# Power_Board_R1.net
KiCad netlist of a schematic drawn in Altium Designer
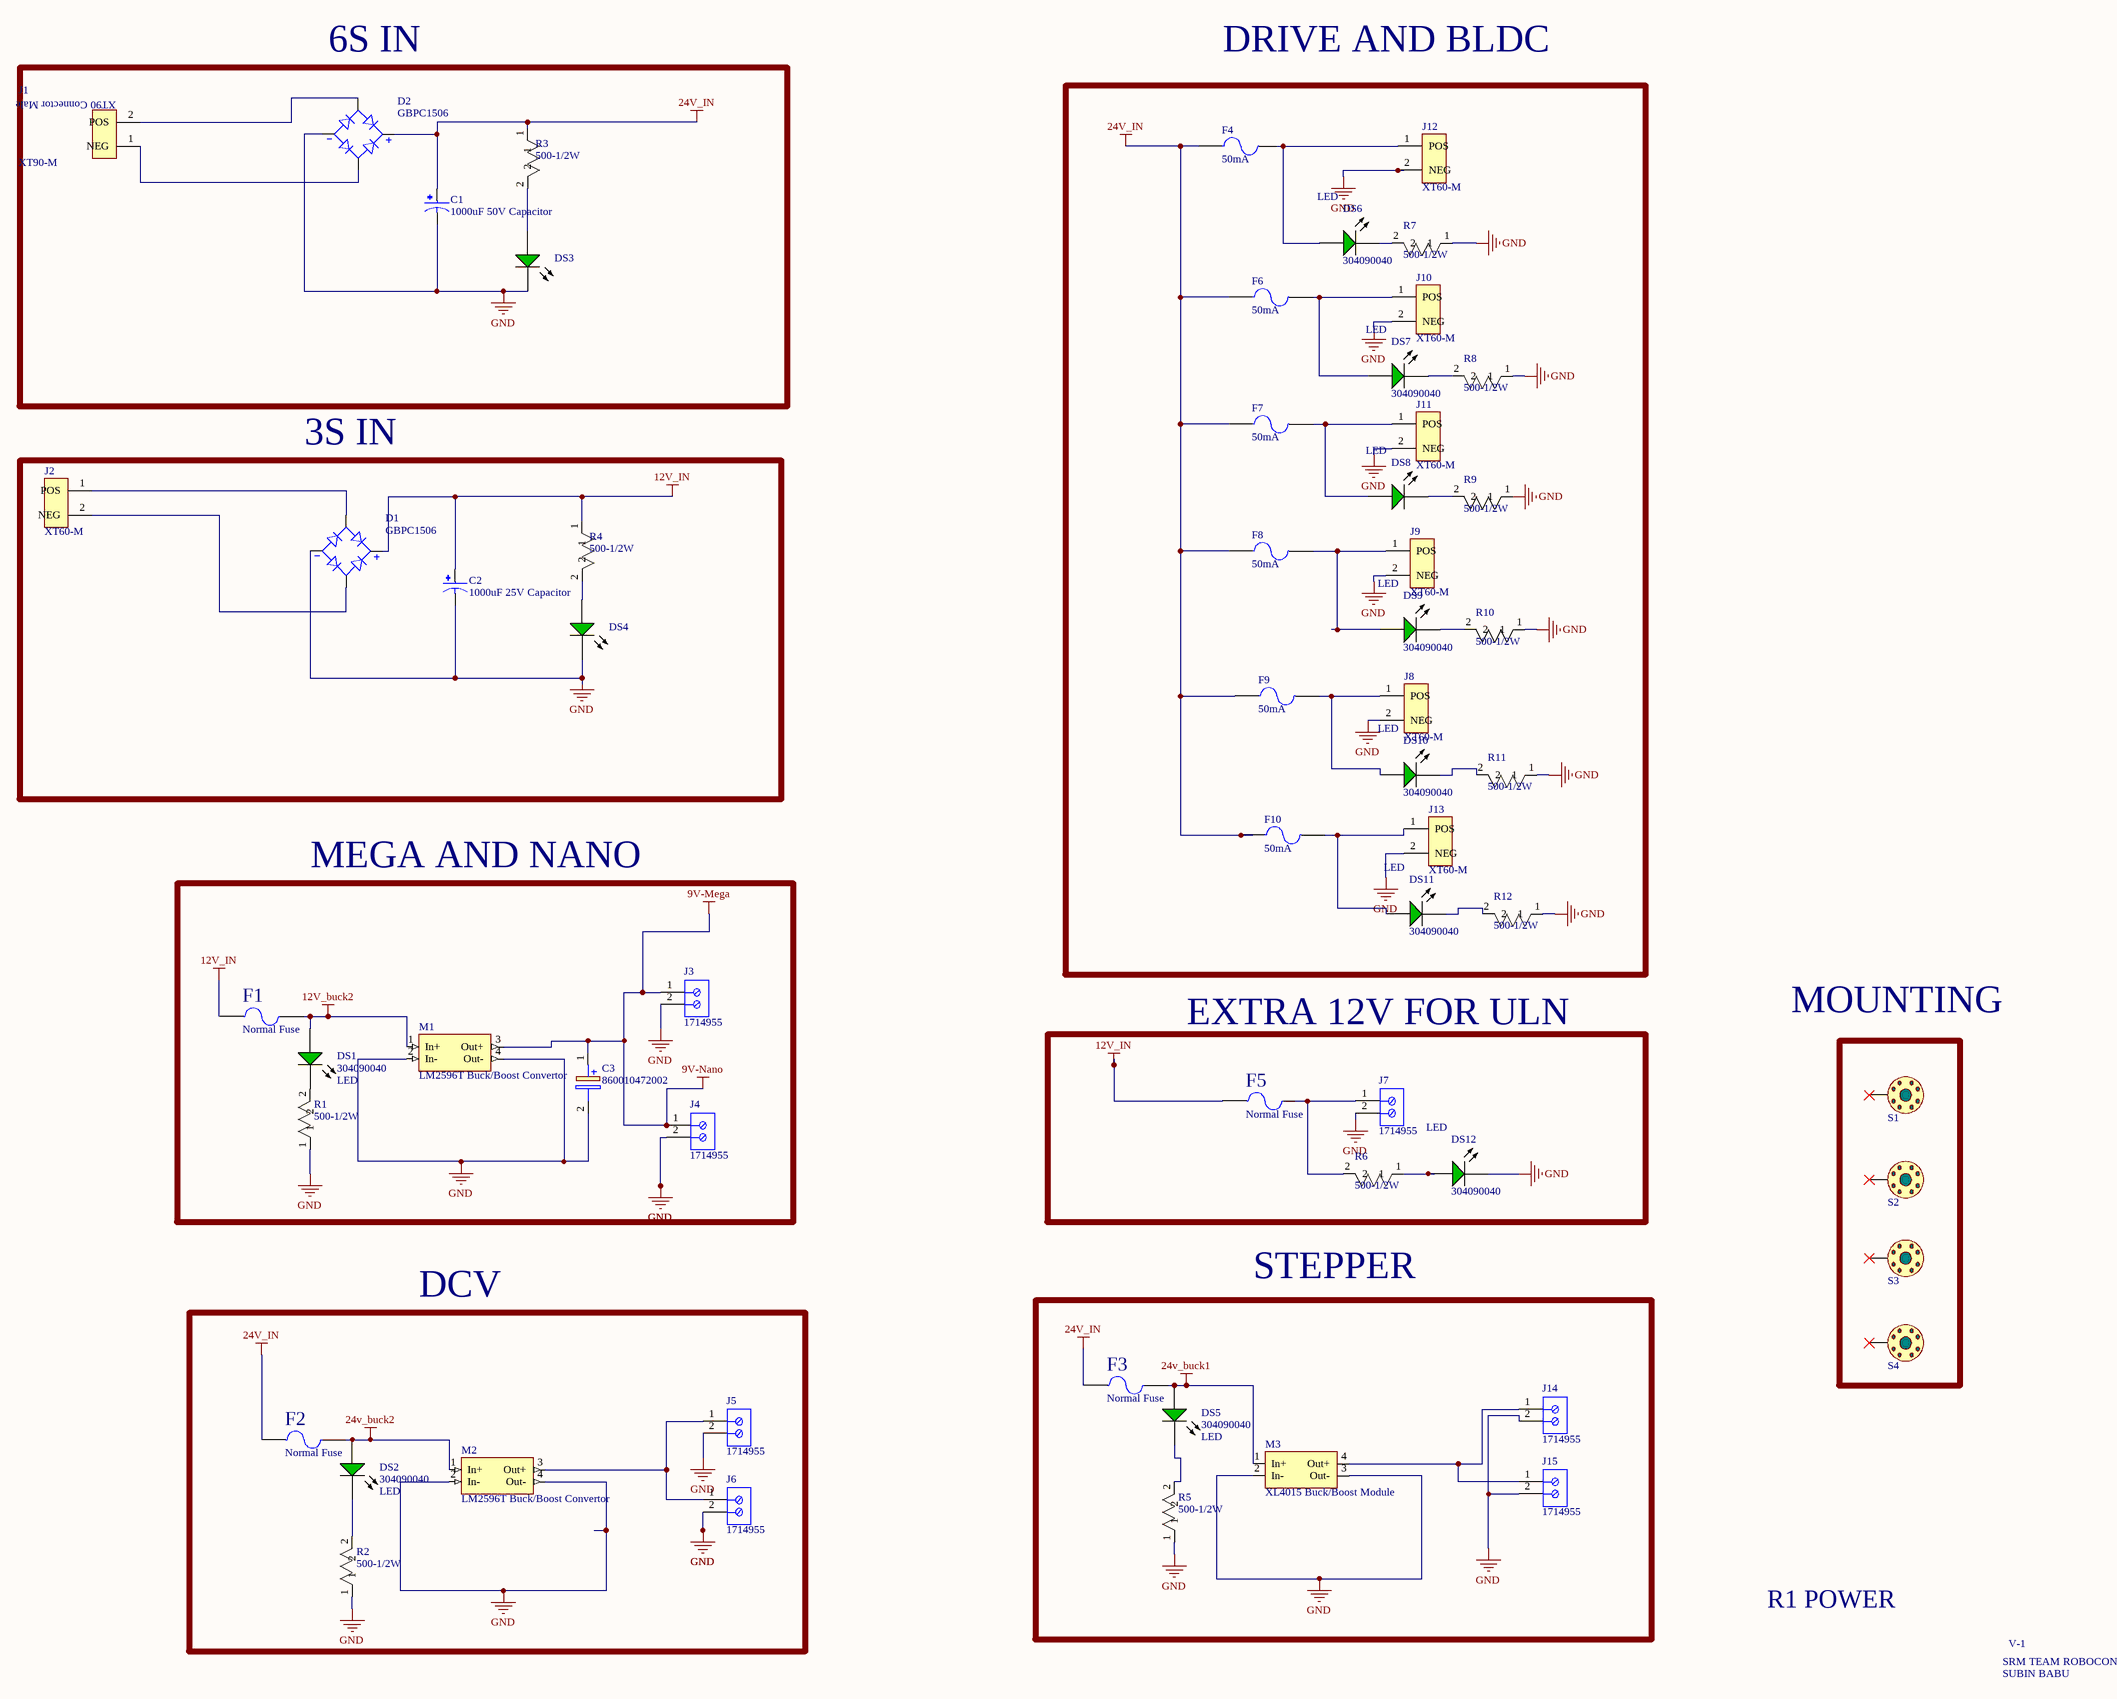
[diagram p0: Power_Board_R1.SchDoc]

(export (version "E")
  (design (tool "Eeschema 10.0.6"))
  (components
    (comp (ref "C1")
      (value "1000uF 50V Capacitor")
      (footprint "1000uF 50V Capacitor")
      (description "CAP ALUM 1000UF 20% 50V RADIAL")
      (fields (field (name "MF") "Panasonic") (field (name "MP") "EEU-HD1H102B"))
      (libsource (lib "R1") (part "1000uF 50V Capacitor"))
    )
    (comp (ref "C2")
      (value "1000uF 25V Capacitor")
      (footprint "1000uF 25V Capacitor")
      (description "CAP ALUM 1000UF 20% 25V RADIAL")
      (fields (field (name "MP") "EEUTA1E102LB") (field (name "MF") "Panasonic"))
      (libsource (lib "R1") (part "1000uF 25V Capacitor"))
    )
    (comp (ref "C3")
      (value "860010472002")
      (footprint "R1:CAPPRD200W52D500H1250")
      (description "Capacitor Polarised")
      (fields (field (name "MOUSER PART NUMBER") "710-860010472002"))
      (libsource (lib "*") (part "860010472002"))
    )
    (comp (ref "D1")
      (value "GBPC1506")
      (footprint "R1:DIOB_GBPC1506")
      (description "Bridge Rectifier Single Phase Standard 600 V QC Terminal GBPC")
      (fields (field (name "MF") "ON Semiconductor"))
      (libsource (lib "R1") (part "GBPC1506"))
    )
    (comp (ref "D2")
      (value "GBPC1506")
      (footprint "R1:DIOB_GBPC1506")
      (description "Bridge Rectifier Single Phase Standard 600 V QC Terminal GBPC")
      (fields (field (name "MF") "ON Semiconductor"))
      (libsource (lib "R1") (part "GBPC1506"))
    )
    (comp (ref "DS1")
      (value "304090040")
      (footprint "LED-2P-2.28-3MM")
      (description "Green LED, 80 mW, 20 mA, -25 to 85 degC, 2-Pin THD")
      (fields (field (name "MANUFACTURER") "Shenzhen CGX") (field (name "COMPONENT TYPE") "LED"))
      (libsource (lib "R1") (part "CMP-007-00006-1"))
    )
    (comp (ref "DS2")
      (value "304090040")
      (footprint "LED-2P-2.28-3MM")
      (description "Green LED, 80 mW, 20 mA, -25 to 85 degC, 2-Pin THD")
      (fields (field (name "MANUFACTURER") "Shenzhen CGX") (field (name "COMPONENT TYPE") "LED"))
      (libsource (lib "R1") (part "CMP-007-00006-1"))
    )
    (comp (ref "DS3")
      (value "~")
      (footprint "LED-2P-2.28-3MM")
      (description "Green LED, 80 mW, 20 mA, -25 to 85 degC, 2-Pin THD")
      (fields (field (name "MANUFACTURER") "Shenzhen CGX"))
      (libsource (lib "R1") (part "LED-GREEN-AK-2"))
    )
    (comp (ref "DS4")
      (value "~")
      (footprint "LED-2P-2.28-3MM")
      (description "Green LED, 80 mW, 20 mA, -25 to 85 degC, 2-Pin THD")
      (fields (field (name "MANUFACTURER") "Shenzhen CGX"))
      (libsource (lib "R1") (part "LED-GREEN-AK-2"))
    )
    (comp (ref "DS5")
      (value "304090040")
      (footprint "LED-2P-2.28-3MM")
      (description "Green LED, 80 mW, 20 mA, -25 to 85 degC, 2-Pin THD")
      (fields (field (name "MANUFACTURER") "Shenzhen CGX") (field (name "COMPONENT TYPE") "LED"))
      (libsource (lib "R1") (part "CMP-007-00006-1"))
    )
    (comp (ref "DS6")
      (value "304090040")
      (footprint "LED-2P-2.28-3MM")
      (description "Green LED, 80 mW, 20 mA, -25 to 85 degC, 2-Pin THD")
      (fields (field (name "MANUFACTURER") "Shenzhen CGX") (field (name "COMPONENT TYPE") "LED"))
      (libsource (lib "R1") (part "CMP-007-00006-1"))
    )
    (comp (ref "DS7")
      (value "304090040")
      (footprint "LED-2P-2.28-3MM")
      (description "Green LED, 80 mW, 20 mA, -25 to 85 degC, 2-Pin THD")
      (fields (field (name "MANUFACTURER") "Shenzhen CGX") (field (name "COMPONENT TYPE") "LED"))
      (libsource (lib "R1") (part "CMP-007-00006-1"))
    )
    (comp (ref "DS8")
      (value "~")
      (footprint "LED-2P-2.28-3MM")
      (description "Green LED, 80 mW, 20 mA, -25 to 85 degC, 2-Pin THD")
      (fields (field (name "MANUFACTURER") "Shenzhen CGX") (field (name "COMPONENT TYPE") "LED"))
      (libsource (lib "R1") (part "CMP-007-00006-1"))
    )
    (comp (ref "DS9")
      (value "304090040")
      (footprint "LED-2P-2.28-3MM")
      (description "Green LED, 80 mW, 20 mA, -25 to 85 degC, 2-Pin THD")
      (fields (field (name "MANUFACTURER") "Shenzhen CGX") (field (name "COMPONENT TYPE") "LED"))
      (libsource (lib "R1") (part "CMP-007-00006-1"))
    )
    (comp (ref "DS10")
      (value "304090040")
      (footprint "LED-2P-2.28-3MM")
      (description "Green LED, 80 mW, 20 mA, -25 to 85 degC, 2-Pin THD")
      (fields (field (name "MANUFACTURER") "Shenzhen CGX") (field (name "COMPONENT TYPE") "LED"))
      (libsource (lib "R1") (part "CMP-007-00006-1"))
    )
    (comp (ref "DS11")
      (value "304090040")
      (footprint "LED-2P-2.28-3MM")
      (description "Green LED, 80 mW, 20 mA, -25 to 85 degC, 2-Pin THD")
      (fields (field (name "MANUFACTURER") "Shenzhen CGX") (field (name "COMPONENT TYPE") "LED"))
      (libsource (lib "R1") (part "CMP-007-00006-1"))
    )
    (comp (ref "DS12")
      (value "304090040")
      (footprint "LED-2P-2.28-3MM")
      (description "Green LED, 80 mW, 20 mA, -25 to 85 degC, 2-Pin THD")
      (fields (field (name "MANUFACTURER") "Shenzhen CGX") (field (name "COMPONENT TYPE") "LED"))
      (libsource (lib "R1") (part "CMP-007-00006-1"))
    )
    (comp (ref "F1") (value "Normal Fuse") (footprint "Fuse") (libsource (lib "R1") (part "Fuse_1")))
    (comp (ref "F2") (value "Normal Fuse") (footprint "Fuse") (libsource (lib "R1") (part "Fuse_1")))
    (comp (ref "F3") (value "Normal Fuse") (footprint "Fuse") (libsource (lib "R1") (part "Fuse_1")))
    (comp (ref "F4") (value "50mA") (footprint "FUSE(ALL SIZE)") (libsource (lib "R1") (part "Fuse")))
    (comp (ref "F5") (value "Normal Fuse") (footprint "Fuse") (libsource (lib "R1") (part "Fuse_1")))
    (comp (ref "F6") (value "50mA") (footprint "FUSE(ALL SIZE)") (libsource (lib "R1") (part "Fuse")))
    (comp (ref "F7") (value "50mA") (footprint "FUSE(ALL SIZE)") (libsource (lib "R1") (part "Fuse")))
    (comp (ref "F8") (value "50mA") (footprint "FUSE(ALL SIZE)") (libsource (lib "R1") (part "Fuse")))
    (comp (ref "F9") (value "50mA") (footprint "FUSE(ALL SIZE)") (libsource (lib "R1") (part "Fuse")))
    (comp (ref "F10") (value "50mA") (footprint "FUSE(ALL SIZE)") (libsource (lib "R1") (part "Fuse")))
    (comp (ref "J1") (value "XT90-M") (footprint "XT90-M") (libsource (lib "R1") (part "XT90-M")))
    (comp (ref "J2")
      (value "XT60-M")
      (footprint "XT-60M")
      (description "Plug; DC supply; XT60; male; PIN: 2; for cable; soldered; 30A; 500V")
      (fields (field (name "MF") "AMASS"))
      (libsource (lib "") (part "XT60-M_1"))
    )
    (comp (ref "J3")
      (value "1714955")
      (footprint "6.35mm 2 Way Screw Terminal")
      (description "PC Terminal Block, Pitch 6.35 mm, 1 x 2 Position, Height 21.5 mm, Tail Lenght 5.1 mm, RoHS, Bulk")
      (fields (field (name "MANUFACTURER") "Phoenix Contact"))
      (libsource (lib "R1") (part "6.35mm 2 Way Screw Terminal"))
    )
    (comp (ref "J4")
      (value "1714955")
      (footprint "6.35mm 2 Way Screw Terminal")
      (description "PC Terminal Block, Pitch 6.35 mm, 1 x 2 Position, Height 21.5 mm, Tail Lenght 5.1 mm, RoHS, Bulk")
      (fields (field (name "MANUFACTURER") "Phoenix Contact"))
      (libsource (lib "R1") (part "6.35mm 2 Way Screw Terminal"))
    )
    (comp (ref "J5")
      (value "1714955")
      (footprint "6.35mm 2 Way Screw Terminal")
      (description "PC Terminal Block, Pitch 6.35 mm, 1 x 2 Position, Height 21.5 mm, Tail Lenght 5.1 mm, RoHS, Bulk")
      (fields (field (name "MANUFACTURER") "Phoenix Contact"))
      (libsource (lib "R1") (part "6.35mm 2 Way Screw Terminal"))
    )
    (comp (ref "J6")
      (value "1714955")
      (footprint "6.35mm 2 Way Screw Terminal")
      (description "PC Terminal Block, Pitch 6.35 mm, 1 x 2 Position, Height 21.5 mm, Tail Lenght 5.1 mm, RoHS, Bulk")
      (fields (field (name "MANUFACTURER") "Phoenix Contact"))
      (libsource (lib "R1") (part "6.35mm 2 Way Screw Terminal"))
    )
    (comp (ref "J7")
      (value "1714955")
      (footprint "6.35mm 2 Way Screw Terminal")
      (description "PC Terminal Block, Pitch 6.35 mm, 1 x 2 Position, Height 21.5 mm, Tail Lenght 5.1 mm, RoHS, Bulk")
      (fields (field (name "MANUFACTURER") "Phoenix Contact"))
      (libsource (lib "R1") (part "6.35mm 2 Way Screw Terminal"))
    )
    (comp (ref "J8")
      (value "XT60-M")
      (footprint "XT-60M")
      (description "Plug; DC supply; XT60; male; PIN: 2; for cable; soldered; 30A; 500V")
      (fields (field (name "MF") "AMASS"))
      (libsource (lib "R1") (part "XT60-M"))
    )
    (comp (ref "J9")
      (value "XT60-M")
      (footprint "XT-60M")
      (description "Plug; DC supply; XT60; male; PIN: 2; for cable; soldered; 30A; 500V")
      (fields (field (name "MF") "AMASS"))
      (libsource (lib "R1") (part "XT60-M"))
    )
    (comp (ref "J10")
      (value "XT60-M")
      (footprint "XT-60M")
      (description "Plug; DC supply; XT60; male; PIN: 2; for cable; soldered; 30A; 500V")
      (fields (field (name "MF") "AMASS"))
      (libsource (lib "R1") (part "XT60-M"))
    )
    (comp (ref "J11")
      (value "XT60-M")
      (footprint "XT-60M")
      (description "Plug; DC supply; XT60; male; PIN: 2; for cable; soldered; 30A; 500V")
      (fields (field (name "MF") "AMASS"))
      (libsource (lib "R1") (part "XT60-M"))
    )
    (comp (ref "J12")
      (value "XT60-M")
      (footprint "XT-60M")
      (description "Plug; DC supply; XT60; male; PIN: 2; for cable; soldered; 30A; 500V")
      (fields (field (name "MF") "AMASS"))
      (libsource (lib "R1") (part "XT60-M"))
    )
    (comp (ref "J13")
      (value "XT60-M")
      (footprint "XT-60M")
      (description "Plug; DC supply; XT60; male; PIN: 2; for cable; soldered; 30A; 500V")
      (fields (field (name "MF") "AMASS"))
      (libsource (lib "R1") (part "XT60-M"))
    )
    (comp (ref "J14")
      (value "1714955")
      (footprint "6.35mm 2 Way Screw Terminal")
      (description "PC Terminal Block, Pitch 6.35 mm, 1 x 2 Position, Height 21.5 mm, Tail Lenght 5.1 mm, RoHS, Bulk")
      (fields (field (name "MANUFACTURER") "Phoenix Contact"))
      (libsource (lib "R1") (part "6.35mm 2 Way Screw Terminal"))
    )
    (comp (ref "J15")
      (value "1714955")
      (footprint "6.35mm 2 Way Screw Terminal")
      (description "PC Terminal Block, Pitch 6.35 mm, 1 x 2 Position, Height 21.5 mm, Tail Lenght 5.1 mm, RoHS, Bulk")
      (fields (field (name "MANUFACTURER") "Phoenix Contact"))
      (libsource (lib "R1") (part "6.35mm 2 Way Screw Terminal"))
    )
    (comp (ref "M1")
      (value "LM2596T Buck/Boost Convertor")
      (footprint "LM2596 MODULE")
      (libsource (lib "R1") (part "LM2596T Buck/Boost Convertor"))
    )
    (comp (ref "M2")
      (value "LM2596T Buck/Boost Convertor")
      (footprint "LM2596 MODULE")
      (libsource (lib "R1") (part "LM2596T Buck/Boost Convertor"))
    )
    (comp (ref "M3")
      (value "XL4015 Buck/Boost Module")
      (footprint "XL4015 Module")
      (libsource (lib "R1") (part "XL4015 Buck/Boost Module"))
    )
    (comp (ref "R1")
      (value "500-1/2W")
      (footprint "R_Axial_DIN0309_L9.0mm_D3.2mm_P12.70mm_Horizontal")
      (libsource (lib "R1") (part "1/2 watt Resistor"))
    )
    (comp (ref "R2")
      (value "500-1/2W")
      (footprint "R_Axial_DIN0309_L9.0mm_D3.2mm_P12.70mm_Horizontal")
      (libsource (lib "R1") (part "1/2 watt Resistor"))
    )
    (comp (ref "R3")
      (value "500-1/2W")
      (footprint "R_Axial_DIN0309_L9.0mm_D3.2mm_P12.70mm_Horizontal")
      (libsource (lib "R1") (part "1/2 watt Resistor"))
    )
    (comp (ref "R4")
      (value "500-1/2W")
      (footprint "R_Axial_DIN0309_L9.0mm_D3.2mm_P12.70mm_Horizontal")
      (libsource (lib "R1") (part "1/2 watt Resistor"))
    )
    (comp (ref "R5")
      (value "500-1/2W")
      (footprint "R_Axial_DIN0309_L9.0mm_D3.2mm_P12.70mm_Horizontal")
      (libsource (lib "R1") (part "1/2 watt Resistor"))
    )
    (comp (ref "R6")
      (value "500-1/2W")
      (footprint "R_Axial_DIN0309_L9.0mm_D3.2mm_P12.70mm_Horizontal")
      (libsource (lib "R1") (part "1/2 watt Resistor"))
    )
    (comp (ref "R7")
      (value "500-1/2W")
      (footprint "R_Axial_DIN0309_L9.0mm_D3.2mm_P12.70mm_Horizontal")
      (libsource (lib "R1") (part "1/2 watt Resistor"))
    )
    (comp (ref "R8")
      (value "500-1/2W")
      (footprint "R_Axial_DIN0309_L9.0mm_D3.2mm_P12.70mm_Horizontal")
      (libsource (lib "R1") (part "1/2 watt Resistor"))
    )
    (comp (ref "R9")
      (value "500-1/2W")
      (footprint "R_Axial_DIN0309_L9.0mm_D3.2mm_P12.70mm_Horizontal")
      (libsource (lib "R1") (part "1/2 watt Resistor"))
    )
    (comp (ref "R10")
      (value "500-1/2W")
      (footprint "R_Axial_DIN0309_L9.0mm_D3.2mm_P12.70mm_Horizontal")
      (libsource (lib "R1") (part "1/2 watt Resistor"))
    )
    (comp (ref "R11")
      (value "500-1/2W")
      (footprint "R_Axial_DIN0309_L9.0mm_D3.2mm_P12.70mm_Horizontal")
      (libsource (lib "R1") (part "1/2 watt Resistor"))
    )
    (comp (ref "R12")
      (value "500-1/2W")
      (footprint "R_Axial_DIN0309_L9.0mm_D3.2mm_P12.70mm_Horizontal")
      (libsource (lib "R1") (part "1/2 watt Resistor"))
    )
    (comp (ref "S1")
      (value "Screw")
      (footprint "SCREW-3MM")
      (description "3mm Screw")
      (fields (field (name "ASID PART NUMBER") "Screw-AS"))
      (libsource (lib "R1") (part "Screw"))
    )
    (comp (ref "S2")
      (value "Screw")
      (footprint "SCREW-3MM")
      (description "3mm Screw")
      (fields (field (name "ASID PART NUMBER") "Screw-AS"))
      (libsource (lib "R1") (part "Screw"))
    )
    (comp (ref "S3")
      (value "Screw")
      (footprint "SCREW-3MM")
      (description "3mm Screw")
      (fields (field (name "ASID PART NUMBER") "Screw-AS"))
      (libsource (lib "R1") (part "Screw"))
    )
    (comp (ref "S4")
      (value "Screw")
      (footprint "SCREW-3MM")
      (description "3mm Screw")
      (fields (field (name "ASID PART NUMBER") "Screw-AS"))
      (libsource (lib "R1") (part "Screw"))
    )
  )
  (nets
    (net (code "1") (name "9V-Mega") (class "Default")
      (node (ref "C3") (pin "1") (pinfunction "+_1") (pintype "passive"))
      (node (ref "J3") (pin "1") (pinfunction "1_1") (pintype "passive"))
      (node (ref "J4") (pin "1") (pinfunction "1_1") (pintype "passive"))
      (node (ref "M1") (pin "3") (pinfunction "Out+_3") (pintype "output"))
    )
    (net (code "2") (name "12V_IN") (class "Default")
      (node (ref "C2") (pin "P") (pinfunction "P_P") (pintype "passive"))
      (node (ref "D1") (pin "P") (pinfunction "P_P") (pintype "passive"))
      (node (ref "F1") (pin "1") (pinfunction "1_1") (pintype "passive"))
      (node (ref "F5") (pin "1") (pinfunction "1_1") (pintype "passive"))
      (node (ref "R4") (pin "1") (pinfunction "1_1") (pintype "passive"))
    )
    (net (code "3") (name "12V_buck2") (class "Default")
      (node (ref "DS1") (pin "1") (pinfunction "A_1") (pintype "passive"))
      (node (ref "F1") (pin "2") (pinfunction "2_2") (pintype "passive"))
      (node (ref "M1") (pin "1") (pinfunction "In+_1") (pintype "input"))
    )
    (net (code "4") (name "24V_IN") (class "Default")
      (node (ref "C1") (pin "P") (pinfunction "P_P") (pintype "passive"))
      (node (ref "D2") (pin "P") (pinfunction "P_P") (pintype "passive"))
      (node (ref "F10") (pin "2") (pinfunction "2_2") (pintype "passive"))
      (node (ref "F2") (pin "1") (pinfunction "1_1") (pintype "passive"))
      (node (ref "F3") (pin "1") (pinfunction "1_1") (pintype "passive"))
      (node (ref "F4") (pin "2") (pinfunction "2_2") (pintype "passive"))
      (node (ref "F6") (pin "2") (pinfunction "2_2") (pintype "passive"))
      (node (ref "F7") (pin "2") (pinfunction "2_2") (pintype "passive"))
      (node (ref "F8") (pin "2") (pinfunction "2_2") (pintype "passive"))
      (node (ref "F9") (pin "2") (pinfunction "2_2") (pintype "passive"))
      (node (ref "R3") (pin "1") (pinfunction "1_1") (pintype "passive"))
    )
    (net (code "5") (name "24v_buck1") (class "Default")
      (node (ref "DS5") (pin "1") (pinfunction "A_1") (pintype "passive"))
      (node (ref "F3") (pin "2") (pinfunction "2_2") (pintype "passive"))
      (node (ref "M3") (pin "1") (pinfunction "In+_1") (pintype "power_in"))
    )
    (net (code "6") (name "24v_buck2") (class "Default")
      (node (ref "DS2") (pin "1") (pinfunction "A_1") (pintype "passive"))
      (node (ref "F2") (pin "2") (pinfunction "2_2") (pintype "passive"))
      (node (ref "M2") (pin "1") (pinfunction "In+_1") (pintype "input"))
    )
    (net (code "7") (name "GND") (class "Default")
      (node (ref "C1") (pin "N") (pinfunction "N_N") (pintype "passive"))
      (node (ref "C2") (pin "N") (pinfunction "N_N") (pintype "passive"))
      (node (ref "C3") (pin "2") (pinfunction "-_2") (pintype "passive"))
      (node (ref "D1") (pin "N") (pinfunction "N_N") (pintype "passive"))
      (node (ref "D2") (pin "N") (pinfunction "N_N") (pintype "passive"))
      (node (ref "DS12") (pin "2") (pinfunction "K_2") (pintype "passive"))
      (node (ref "DS3") (pin "2") (pinfunction "K_2") (pintype "passive"))
      (node (ref "DS4") (pin "2") (pinfunction "K_2") (pintype "passive"))
      (node (ref "J10") (pin "2") (pinfunction "NEG_2") (pintype "passive"))
      (node (ref "J11") (pin "2") (pinfunction "NEG_2") (pintype "passive"))
      (node (ref "J12") (pin "2") (pinfunction "NEG_2") (pintype "passive"))
      (node (ref "J13") (pin "2") (pinfunction "NEG_2") (pintype "passive"))
      (node (ref "J14") (pin "2") (pinfunction "2_2") (pintype "passive"))
      (node (ref "J15") (pin "2") (pinfunction "2_2") (pintype "passive"))
      (node (ref "J3") (pin "2") (pinfunction "2_2") (pintype "passive"))
      (node (ref "J4") (pin "2") (pinfunction "2_2") (pintype "passive"))
      (node (ref "J5") (pin "2") (pinfunction "2_2") (pintype "passive"))
      (node (ref "J6") (pin "2") (pinfunction "2_2") (pintype "passive"))
      (node (ref "J7") (pin "2") (pinfunction "2_2") (pintype "passive"))
      (node (ref "J8") (pin "2") (pinfunction "NEG_2") (pintype "passive"))
      (node (ref "J9") (pin "2") (pinfunction "NEG_2") (pintype "passive"))
      (node (ref "M1") (pin "2") (pinfunction "In-_2") (pintype "input"))
      (node (ref "M1") (pin "4") (pinfunction "Out-_4") (pintype "output"))
      (node (ref "M2") (pin "2") (pinfunction "In-_2") (pintype "input"))
      (node (ref "M2") (pin "4") (pinfunction "Out-_4") (pintype "output"))
      (node (ref "M3") (pin "2") (pinfunction "In-_2") (pintype "power_in"))
      (node (ref "M3") (pin "3") (pinfunction "Out-_3") (pintype "power_in"))
      (node (ref "R1") (pin "1") (pinfunction "1_1") (pintype "passive"))
      (node (ref "R10") (pin "1") (pinfunction "1_1") (pintype "passive"))
      (node (ref "R11") (pin "1") (pinfunction "1_1") (pintype "passive"))
      (node (ref "R12") (pin "1") (pinfunction "1_1") (pintype "passive"))
      (node (ref "R2") (pin "1") (pinfunction "1_1") (pintype "passive"))
      (node (ref "R5") (pin "1") (pinfunction "1_1") (pintype "passive"))
      (node (ref "R7") (pin "1") (pinfunction "1_1") (pintype "passive"))
      (node (ref "R8") (pin "1") (pinfunction "1_1") (pintype "passive"))
      (node (ref "R9") (pin "1") (pinfunction "1_1") (pintype "passive"))
    )
    (net (code "8") (name "Net-(DS1-K)") (class "Default")
      (node (ref "DS1") (pin "2") (pinfunction "K_2") (pintype "passive"))
      (node (ref "R1") (pin "2") (pinfunction "2_2") (pintype "passive"))
    )
    (net (code "9") (name "Net-(DS2-K)") (class "Default")
      (node (ref "DS2") (pin "2") (pinfunction "K_2") (pintype "passive"))
      (node (ref "R2") (pin "2") (pinfunction "2_2") (pintype "passive"))
    )
    (net (code "10") (name "Net-(DS3-A)") (class "Default")
      (node (ref "DS3") (pin "1") (pinfunction "A_1") (pintype "passive"))
      (node (ref "R3") (pin "2") (pinfunction "2_2") (pintype "passive"))
    )
    (net (code "11") (name "Net-(DS4-A)") (class "Default")
      (node (ref "DS4") (pin "1") (pinfunction "A_1") (pintype "passive"))
      (node (ref "R4") (pin "2") (pinfunction "2_2") (pintype "passive"))
    )
    (net (code "12") (name "Net-(DS5-K)") (class "Default")
      (node (ref "DS5") (pin "2") (pinfunction "K_2") (pintype "passive"))
      (node (ref "R5") (pin "2") (pinfunction "2_2") (pintype "passive"))
    )
    (net (code "13") (name "Net-(DS6-A)") (class "Default")
      (node (ref "DS6") (pin "1") (pinfunction "A_1") (pintype "passive"))
      (node (ref "F4") (pin "1") (pinfunction "1_1") (pintype "passive"))
      (node (ref "J12") (pin "1") (pinfunction "POS_1") (pintype "passive"))
    )
    (net (code "14") (name "Net-(DS6-K)") (class "Default")
      (node (ref "DS6") (pin "2") (pinfunction "K_2") (pintype "passive"))
      (node (ref "R7") (pin "2") (pinfunction "2_2") (pintype "passive"))
    )
    (net (code "15") (name "Net-(DS7-A)") (class "Default")
      (node (ref "DS7") (pin "1") (pinfunction "A_1") (pintype "passive"))
      (node (ref "F6") (pin "1") (pinfunction "1_1") (pintype "passive"))
      (node (ref "J10") (pin "1") (pinfunction "POS_1") (pintype "passive"))
    )
    (net (code "16") (name "Net-(DS7-K)") (class "Default")
      (node (ref "DS7") (pin "2") (pinfunction "K_2") (pintype "passive"))
      (node (ref "R8") (pin "2") (pinfunction "2_2") (pintype "passive"))
    )
    (net (code "17") (name "Net-(DS8-A)") (class "Default")
      (node (ref "DS8") (pin "1") (pinfunction "A_1") (pintype "passive"))
      (node (ref "F7") (pin "1") (pinfunction "1_1") (pintype "passive"))
      (node (ref "J11") (pin "1") (pinfunction "POS_1") (pintype "passive"))
    )
    (net (code "18") (name "Net-(DS8-K)") (class "Default")
      (node (ref "DS8") (pin "2") (pinfunction "K_2") (pintype "passive"))
      (node (ref "R9") (pin "2") (pinfunction "2_2") (pintype "passive"))
    )
    (net (code "19") (name "Net-(DS9-A)") (class "Default")
      (node (ref "DS9") (pin "1") (pinfunction "A_1") (pintype "passive"))
      (node (ref "F8") (pin "1") (pinfunction "1_1") (pintype "passive"))
      (node (ref "J9") (pin "1") (pinfunction "POS_1") (pintype "passive"))
    )
    (net (code "20") (name "Net-(DS9-K)") (class "Default")
      (node (ref "DS9") (pin "2") (pinfunction "K_2") (pintype "passive"))
      (node (ref "R10") (pin "2") (pinfunction "2_2") (pintype "passive"))
    )
    (net (code "21") (name "Net-(DS10-A)") (class "Default")
      (node (ref "DS10") (pin "1") (pinfunction "A_1") (pintype "passive"))
      (node (ref "F9") (pin "1") (pinfunction "1_1") (pintype "passive"))
      (node (ref "J8") (pin "1") (pinfunction "POS_1") (pintype "passive"))
    )
    (net (code "22") (name "Net-(DS10-K)") (class "Default")
      (node (ref "DS10") (pin "2") (pinfunction "K_2") (pintype "passive"))
      (node (ref "R11") (pin "2") (pinfunction "2_2") (pintype "passive"))
    )
    (net (code "23") (name "Net-(DS11-A)") (class "Default")
      (node (ref "DS11") (pin "1") (pinfunction "A_1") (pintype "passive"))
      (node (ref "F10") (pin "1") (pinfunction "1_1") (pintype "passive"))
      (node (ref "J13") (pin "1") (pinfunction "POS_1") (pintype "passive"))
    )
    (net (code "24") (name "Net-(DS11-K)") (class "Default")
      (node (ref "DS11") (pin "2") (pinfunction "K_2") (pintype "passive"))
      (node (ref "R12") (pin "2") (pinfunction "2_2") (pintype "passive"))
    )
    (net (code "25") (name "Net-(DS12-A)") (class "Default")
      (node (ref "DS12") (pin "1") (pinfunction "A_1") (pintype "passive"))
      (node (ref "R6") (pin "1") (pinfunction "1_1") (pintype "passive"))
    )
    (net (code "26") (name "Net-(F5-Pad2)") (class "Default")
      (node (ref "F5") (pin "2") (pinfunction "2_2") (pintype "passive"))
      (node (ref "J7") (pin "1") (pinfunction "1_1") (pintype "passive"))
      (node (ref "R6") (pin "2") (pinfunction "2_2") (pintype "passive"))
    )
    (net (code "27") (name "Net-(J1-NEG)") (class "Default")
      (node (ref "D2") (pin "AC1") (pinfunction "AC1_AC1") (pintype "passive"))
      (node (ref "J1") (pin "1") (pinfunction "NEG_1") (pintype "passive"))
    )
    (net (code "28") (name "Net-(J1-POS)") (class "Default")
      (node (ref "D2") (pin "AC2") (pinfunction "AC2_AC2") (pintype "passive"))
      (node (ref "J1") (pin "2") (pinfunction "POS_2") (pintype "passive"))
    )
    (net (code "29") (name "Net-(J2-NEG)") (class "Default")
      (node (ref "D1") (pin "AC1") (pinfunction "AC1_AC1") (pintype "passive"))
      (node (ref "J2") (pin "2") (pinfunction "NEG_2") (pintype "passive"))
    )
    (net (code "30") (name "Net-(J2-POS)") (class "Default")
      (node (ref "D1") (pin "AC2") (pinfunction "AC2_AC2") (pintype "passive"))
      (node (ref "J2") (pin "1") (pinfunction "POS_1") (pintype "passive"))
    )
    (net (code "31") (name "Net-(M2-Out+)") (class "Default")
      (node (ref "J5") (pin "1") (pinfunction "1_1") (pintype "passive"))
      (node (ref "J6") (pin "1") (pinfunction "1_1") (pintype "passive"))
      (node (ref "M2") (pin "3") (pinfunction "Out+_3") (pintype "output"))
    )
    (net (code "32") (name "Net-(M3-Out+)") (class "Default")
      (node (ref "J14") (pin "1") (pinfunction "1_1") (pintype "passive"))
      (node (ref "J15") (pin "1") (pinfunction "1_1") (pintype "passive"))
      (node (ref "M3") (pin "4") (pinfunction "Out+_4") (pintype "power_in"))
    )
    (net (code "33") (name "unconnected-(S1-Pad0)") (class "Default")
      (node (ref "S1") (pin "0") (pinfunction "0_0") (pintype "passive+no_connect"))
    )
    (net (code "34") (name "unconnected-(S2-Pad0)") (class "Default")
      (node (ref "S2") (pin "0") (pinfunction "0_0") (pintype "passive+no_connect"))
    )
    (net (code "35") (name "unconnected-(S3-Pad0)") (class "Default")
      (node (ref "S3") (pin "0") (pinfunction "0_0") (pintype "passive+no_connect"))
    )
    (net (code "36") (name "unconnected-(S4-Pad0)") (class "Default")
      (node (ref "S4") (pin "0") (pinfunction "0_0") (pintype "passive+no_connect"))
    )
  )
)
